# ver2.net
KiCad netlist of a schematic drawn in EAGLE
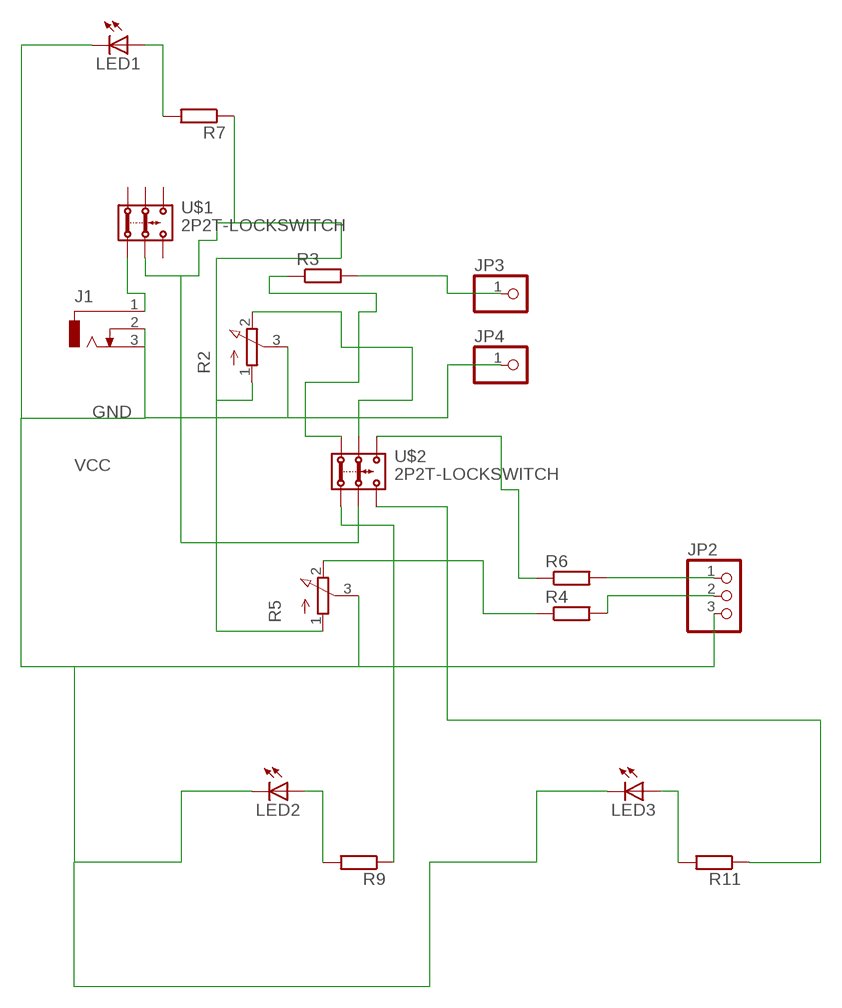
[diagram p0: schematic, sheet 1]

(export (version "E")
  (design (tool "Eeschema 10.0.6"))
  (components
    (comp (ref "J1")
      (value "DCJ0303")
      (footprint "eagle-import:DCJ0303")
      (libsource (lib "eagle-import") (part "DCJ0303"))
    )
    (comp (ref "JP2")
      (value "PINHD-1X3")
      (footprint "eagle-import:1X03")
      (libsource (lib "eagle-import") (part "PINHD-1X3"))
    )
    (comp (ref "JP3")
      (value "PINHD-1X11X01_CHANDIMA")
      (footprint "eagle-import:1X01_CHANDIMA")
      (libsource (lib "eagle-import") (part "PINHD-1X11X01_CHANDIMA"))
    )
    (comp (ref "JP4")
      (value "PINHD-1X11X01_CHANDIMA")
      (footprint "eagle-import:1X01_CHANDIMA")
      (libsource (lib "eagle-import") (part "PINHD-1X11X01_CHANDIMA"))
    )
    (comp (ref "LED1")
      (value "LEDLED5MM-CHANDIMA")
      (footprint "eagle-import:LED5MM-CHANDIMA")
      (libsource (lib "eagle-import") (part "LEDLED5MM-CHANDIMA"))
    )
    (comp (ref "LED2")
      (value "LEDLED5MM-CHANDIMA")
      (footprint "eagle-import:LED5MM-CHANDIMA")
      (libsource (lib "eagle-import") (part "LEDLED5MM-CHANDIMA"))
    )
    (comp (ref "LED3")
      (value "LEDLED5MM-CHANDIMA")
      (footprint "eagle-import:LED5MM-CHANDIMA")
      (libsource (lib "eagle-import") (part "LEDLED5MM-CHANDIMA"))
    )
    (comp (ref "R2")
      (value "3RP/1610N3RP_CHANDIMA")
      (footprint "eagle-import:3RP_1610N_CHANDIMA")
      (libsource (lib "eagle-import") (part "3RP/1610N3RP_CHANDIMA"))
    )
    (comp (ref "R3")
      (value "R-EU_0207/10_CHANDIMA")
      (footprint "eagle-import:0207_10_CHANDIMA")
      (libsource (lib "eagle-import") (part "R-EU_0207/10_CHANDIMA"))
    )
    (comp (ref "R4")
      (value "R-EU_0207/10_CHANDIMA")
      (footprint "eagle-import:0207_10_CHANDIMA")
      (libsource (lib "eagle-import") (part "R-EU_0207/10_CHANDIMA"))
    )
    (comp (ref "R5")
      (value "3RP/1610N3RP_CHANDIMA")
      (footprint "eagle-import:3RP_1610N_CHANDIMA")
      (libsource (lib "eagle-import") (part "3RP/1610N3RP_CHANDIMA"))
    )
    (comp (ref "R6")
      (value "R-EU_0207/10_CHANDIMA")
      (footprint "eagle-import:0207_10_CHANDIMA")
      (libsource (lib "eagle-import") (part "R-EU_0207/10_CHANDIMA"))
    )
    (comp (ref "R7")
      (value "R-EU_0207/10_CHANDIMA")
      (footprint "eagle-import:0207_10_CHANDIMA")
      (libsource (lib "eagle-import") (part "R-EU_0207/10_CHANDIMA"))
    )
    (comp (ref "R9")
      (value "R-EU_0207/10_CHANDIMA")
      (footprint "eagle-import:0207_10_CHANDIMA")
      (libsource (lib "eagle-import") (part "R-EU_0207/10_CHANDIMA"))
    )
    (comp (ref "R11")
      (value "R-EU_0207/10_CHANDIMA")
      (footprint "eagle-import:0207_10_CHANDIMA")
      (libsource (lib "eagle-import") (part "R-EU_0207/10_CHANDIMA"))
    )
    (comp (ref "U$1")
      (value "2P2T-LOCKSWITCH")
      (footprint "eagle-import:2P2T-LOCKSWITCH")
      (libsource (lib "eagle-import") (part "2P2T-LOCKSWITCH"))
    )
    (comp (ref "U$2")
      (value "2P2T-LOCKSWITCH")
      (footprint "eagle-import:2P2T-LOCKSWITCH")
      (libsource (lib "eagle-import") (part "2P2T-LOCKSWITCH"))
    )
  )
  (nets
    (net (code "1") (name "/GND") (class "Default")
      (node (ref "J1") (pin "2") (pinfunction "2_2") (pintype "passive"))
      (node (ref "J1") (pin "3") (pinfunction "3_3") (pintype "passive"))
      (node (ref "JP2") (pin "3") (pinfunction "3_3") (pintype "passive"))
      (node (ref "JP4") (pin "1") (pinfunction "1_1") (pintype "passive"))
      (node (ref "LED1") (pin "K") (pinfunction "C_K") (pintype "passive"))
      (node (ref "LED2") (pin "K") (pinfunction "C_K") (pintype "passive"))
      (node (ref "LED3") (pin "K") (pinfunction "C_K") (pintype "passive"))
      (node (ref "R2") (pin "3") (pinfunction "S_3") (pintype "passive"))
      (node (ref "R5") (pin "3") (pinfunction "S_3") (pintype "passive"))
    )
    (net (code "2") (name "/VCC") (class "Default")
      (node (ref "R2") (pin "1") (pinfunction "A_1") (pintype "passive"))
      (node (ref "R5") (pin "1") (pinfunction "A_1") (pintype "passive"))
      (node (ref "R7") (pin "1") (pinfunction "1_1") (pintype "passive"))
      (node (ref "U$1") (pin "2.2") (pinfunction "2.2_2.2") (pintype "passive"))
      (node (ref "U$2") (pin "2.2") (pinfunction "2.2_2.2") (pintype "passive"))
    )
    (net (code "3") (name "Net-(J1-Pad1)") (class "Default")
      (node (ref "J1") (pin "1") (pinfunction "1_1") (pintype "passive"))
      (node (ref "U$1") (pin "1.2") (pinfunction "1.2_1.2") (pintype "passive"))
    )
    (net (code "4") (name "Net-(JP2-Pad1)") (class "Default")
      (node (ref "JP2") (pin "1") (pinfunction "1_1") (pintype "passive"))
      (node (ref "R6") (pin "2") (pinfunction "2_2") (pintype "passive"))
    )
    (net (code "5") (name "Net-(JP2-Pad2)") (class "Default")
      (node (ref "JP2") (pin "2") (pinfunction "2_2") (pintype "passive"))
      (node (ref "R4") (pin "2") (pinfunction "2_2") (pintype "passive"))
    )
    (net (code "6") (name "Net-(JP3-Pad1)") (class "Default")
      (node (ref "JP3") (pin "1") (pinfunction "1_1") (pintype "passive"))
      (node (ref "R3") (pin "2") (pinfunction "2_2") (pintype "passive"))
    )
    (net (code "7") (name "Net-(LED1-PadA)") (class "Default")
      (node (ref "LED1") (pin "A") (pinfunction "A_A") (pintype "passive"))
      (node (ref "R7") (pin "2") (pinfunction "2_2") (pintype "passive"))
    )
    (net (code "8") (name "Net-(LED2-PadA)") (class "Default")
      (node (ref "LED2") (pin "A") (pinfunction "A_A") (pintype "passive"))
      (node (ref "R9") (pin "2") (pinfunction "2_2") (pintype "passive"))
    )
    (net (code "9") (name "Net-(LED3-PadA)") (class "Default")
      (node (ref "LED3") (pin "A") (pinfunction "A_A") (pintype "passive"))
      (node (ref "R11") (pin "2") (pinfunction "2_2") (pintype "passive"))
    )
    (net (code "10") (name "Net-(R2-E)") (class "Default")
      (node (ref "R2") (pin "2") (pinfunction "E_2") (pintype "passive"))
      (node (ref "U$2") (pin "2.1") (pinfunction "2.1_2.1") (pintype "passive"))
    )
    (net (code "11") (name "Net-(R3-Pad1)") (class "Default")
      (node (ref "R3") (pin "1") (pinfunction "1_1") (pintype "passive"))
      (node (ref "U$2") (pin "1.1") (pinfunction "1.1_1.1") (pintype "passive"))
    )
    (net (code "12") (name "Net-(R5-E)") (class "Default")
      (node (ref "R4") (pin "1") (pinfunction "1_1") (pintype "passive"))
      (node (ref "R5") (pin "2") (pinfunction "E_2") (pintype "passive"))
    )
    (net (code "13") (name "Net-(R6-Pad1)") (class "Default")
      (node (ref "R6") (pin "1") (pinfunction "1_1") (pintype "passive"))
      (node (ref "U$2") (pin "3.1") (pinfunction "3.1_3.1") (pintype "passive"))
    )
    (net (code "14") (name "Net-(R9-Pad1)") (class "Default")
      (node (ref "R9") (pin "1") (pinfunction "1_1") (pintype "passive"))
      (node (ref "U$2") (pin "1.2") (pinfunction "1.2_1.2") (pintype "passive"))
    )
    (net (code "15") (name "Net-(R11-Pad1)") (class "Default")
      (node (ref "R11") (pin "1") (pinfunction "1_1") (pintype "passive"))
      (node (ref "U$2") (pin "3.2") (pinfunction "3.2_3.2") (pintype "passive"))
    )
    (net (code "16") (name "unconnected-(U$1-Pad1.1)") (class "Default")
      (node (ref "U$1") (pin "1.1") (pinfunction "1.1_1.1") (pintype "passive"))
    )
    (net (code "17") (name "unconnected-(U$1-Pad2.1)") (class "Default")
      (node (ref "U$1") (pin "2.1") (pinfunction "2.1_2.1") (pintype "passive"))
    )
    (net (code "18") (name "unconnected-(U$1-Pad3.1)") (class "Default")
      (node (ref "U$1") (pin "3.1") (pinfunction "3.1_3.1") (pintype "passive"))
    )
    (net (code "19") (name "unconnected-(U$1-Pad3.2)") (class "Default")
      (node (ref "U$1") (pin "3.2") (pinfunction "3.2_3.2") (pintype "passive"))
    )
  )
)
